# clock.net
KiCad netlist of a schematic drawn in EAGLE
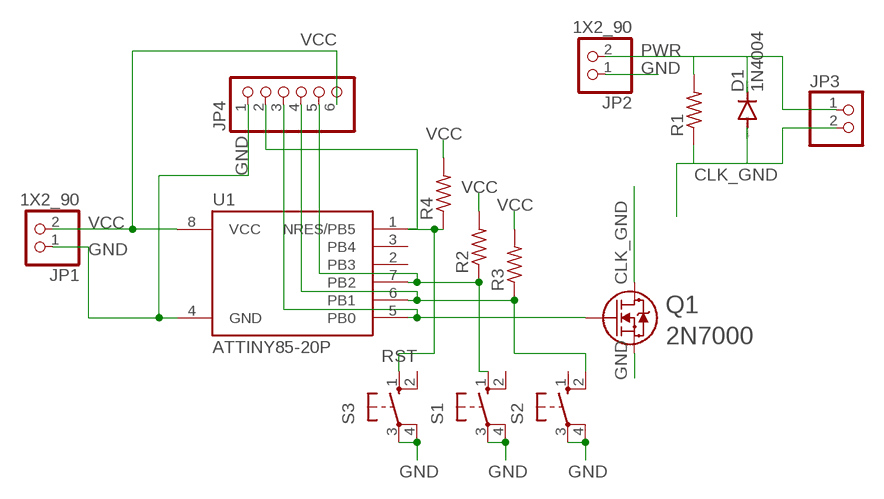
[diagram p0: schematic, sheet 1]

(export (version "E")
  (design (tool "Eeschema 10.0.6"))
  (components
    (comp (ref "D1")
      (value "1N4004")
      (footprint "eagle-import:DO41-10")
      (libsource (lib "eagle-import") (part "1N4004"))
    )
    (comp (ref "JP1")
      (value "1X2_90")
      (footprint "eagle-import:1X02_90")
      (libsource (lib "eagle-import") (part "1X2_90"))
    )
    (comp (ref "JP2")
      (value "1X2_90")
      (footprint "eagle-import:1X02_90")
      (libsource (lib "eagle-import") (part "1X2_90"))
    )
    (comp (ref "JP3")
      (value "PINHD-1X2")
      (footprint "eagle-import:1X02")
      (libsource (lib "eagle-import") (part "PINHD-1X2"))
    )
    (comp (ref "JP4")
      (value "PINHD-1X6")
      (footprint "eagle-import:1X06")
      (libsource (lib "eagle-import") (part "PINHD-1X6"))
    )
    (comp (ref "Q1")
      (value "2N7000")
      (footprint "eagle-import:TO-92")
      (libsource (lib "eagle-import") (part "2N7000"))
    )
    (comp (ref "R1")
      (value "R-US_0204/7")
      (footprint "eagle-import:0204_7")
      (libsource (lib "eagle-import") (part "R-US_0204/7"))
    )
    (comp (ref "R2")
      (value "R-US_0204/7")
      (footprint "eagle-import:0204_7")
      (libsource (lib "eagle-import") (part "R-US_0204/7"))
    )
    (comp (ref "R3")
      (value "R-US_0204/7")
      (footprint "eagle-import:0204_7")
      (libsource (lib "eagle-import") (part "R-US_0204/7"))
    )
    (comp (ref "R4")
      (value "R-US_0204/7")
      (footprint "eagle-import:0204_7")
      (libsource (lib "eagle-import") (part "R-US_0204/7"))
    )
    (comp (ref "S1")
      (value "10-XX")
      (footprint "eagle-import:B3F-10XX")
      (fields (field (name "MPN") "B3F-1000"))
      (libsource (lib "eagle-import") (part "10-XX"))
    )
    (comp (ref "S2")
      (value "10-XX")
      (footprint "eagle-import:B3F-10XX")
      (fields (field (name "MPN") "B3F-1000"))
      (libsource (lib "eagle-import") (part "10-XX"))
    )
    (comp (ref "S3")
      (value "10-XX")
      (footprint "eagle-import:B3F-10XX")
      (fields (field (name "MPN") "B3F-1000"))
      (libsource (lib "eagle-import") (part "10-XX"))
    )
    (comp (ref "U1")
      (value "ATTINY85-20P")
      (footprint "eagle-import:PDIP08_300MIL")
      (libsource (lib "eagle-import") (part "ATTINY85P-20"))
    )
  )
  (nets
    (net (code "1") (name "/CLK_GND") (class "Default")
      (node (ref "D1") (pin "A") (pinfunction "A_A") (pintype "passive"))
      (node (ref "JP3") (pin "2") (pinfunction "2_2") (pintype "passive"))
      (node (ref "Q1") (pin "3") (pinfunction "2_3") (pintype "passive"))
      (node (ref "R1") (pin "1") (pinfunction "1_1") (pintype "passive"))
    )
    (net (code "2") (name "/GND") (class "Default")
      (node (ref "JP1") (pin "1") (pinfunction "1_1") (pintype "passive"))
      (node (ref "JP2") (pin "1") (pinfunction "1_1") (pintype "passive"))
      (node (ref "JP4") (pin "1") (pinfunction "1_1") (pintype "passive"))
      (node (ref "Q1") (pin "1") (pinfunction "3_1") (pintype "passive"))
      (node (ref "S1") (pin "3") (pinfunction "P_3") (pintype "passive"))
      (node (ref "S1") (pin "4") (pinfunction "P1_4") (pintype "passive"))
      (node (ref "S2") (pin "3") (pinfunction "P_3") (pintype "passive"))
      (node (ref "S2") (pin "4") (pinfunction "P1_4") (pintype "passive"))
      (node (ref "S3") (pin "3") (pinfunction "P_3") (pintype "passive"))
      (node (ref "S3") (pin "4") (pinfunction "P1_4") (pintype "passive"))
      (node (ref "U1") (pin "4") (pinfunction "GND_4") (pintype "power_in"))
    )
    (net (code "3") (name "/PWR") (class "Default")
      (node (ref "D1") (pin "C") (pinfunction "C_C") (pintype "passive"))
      (node (ref "JP2") (pin "2") (pinfunction "2_2") (pintype "passive"))
      (node (ref "JP3") (pin "1") (pinfunction "1_1") (pintype "passive"))
      (node (ref "R1") (pin "2") (pinfunction "2_2") (pintype "passive"))
    )
    (net (code "4") (name "/RST") (class "Default")
      (node (ref "JP4") (pin "2") (pinfunction "2_2") (pintype "passive"))
      (node (ref "R4") (pin "1") (pinfunction "1_1") (pintype "passive"))
      (node (ref "S3") (pin "1") (pinfunction "S_1") (pintype "passive"))
      (node (ref "U1") (pin "1") (pinfunction "NRES/PB5_1") (pintype "bidirectional"))
    )
    (net (code "5") (name "/VCC") (class "Default")
      (node (ref "JP1") (pin "2") (pinfunction "2_2") (pintype "passive"))
      (node (ref "JP4") (pin "6") (pinfunction "6_6") (pintype "passive"))
      (node (ref "R2") (pin "2") (pinfunction "2_2") (pintype "passive"))
      (node (ref "R3") (pin "2") (pinfunction "2_2") (pintype "passive"))
      (node (ref "R4") (pin "2") (pinfunction "2_2") (pintype "passive"))
      (node (ref "U1") (pin "8") (pinfunction "VCC_8") (pintype "power_in"))
    )
    (net (code "6") (name "Net-(Q1-1)") (class "Default")
      (node (ref "JP4") (pin "3") (pinfunction "3_3") (pintype "passive"))
      (node (ref "Q1") (pin "2") (pinfunction "1_2") (pintype "passive"))
      (node (ref "U1") (pin "5") (pinfunction "PB0_5") (pintype "bidirectional"))
    )
    (net (code "7") (name "Net-(S1-S)") (class "Default")
      (node (ref "JP4") (pin "5") (pinfunction "5_5") (pintype "passive"))
      (node (ref "R2") (pin "1") (pinfunction "1_1") (pintype "passive"))
      (node (ref "S1") (pin "1") (pinfunction "S_1") (pintype "passive"))
      (node (ref "U1") (pin "7") (pinfunction "PB2_7") (pintype "bidirectional"))
    )
    (net (code "8") (name "Net-(S2-S1)") (class "Default")
      (node (ref "JP4") (pin "4") (pinfunction "4_4") (pintype "passive"))
      (node (ref "R3") (pin "1") (pinfunction "1_1") (pintype "passive"))
      (node (ref "S2") (pin "2") (pinfunction "S1_2") (pintype "passive"))
      (node (ref "U1") (pin "6") (pinfunction "PB1_6") (pintype "bidirectional"))
    )
    (net (code "9") (name "unconnected-(S1-S1-Pad2)") (class "Default")
      (node (ref "S1") (pin "2") (pinfunction "S1_2") (pintype "passive"))
    )
    (net (code "10") (name "unconnected-(S2-S-Pad1)") (class "Default")
      (node (ref "S2") (pin "1") (pinfunction "S_1") (pintype "passive"))
    )
    (net (code "11") (name "unconnected-(S3-S1-Pad2)") (class "Default")
      (node (ref "S3") (pin "2") (pinfunction "S1_2") (pintype "passive"))
    )
    (net (code "12") (name "unconnected-(U1-PB3-Pad2)") (class "Default")
      (node (ref "U1") (pin "2") (pinfunction "PB3_2") (pintype "bidirectional"))
    )
    (net (code "13") (name "unconnected-(U1-PB4-Pad3)") (class "Default")
      (node (ref "U1") (pin "3") (pinfunction "PB4_3") (pintype "bidirectional"))
    )
  )
)
